# BLUETOOTH.net
KiCad netlist of a schematic drawn in Altium Designer
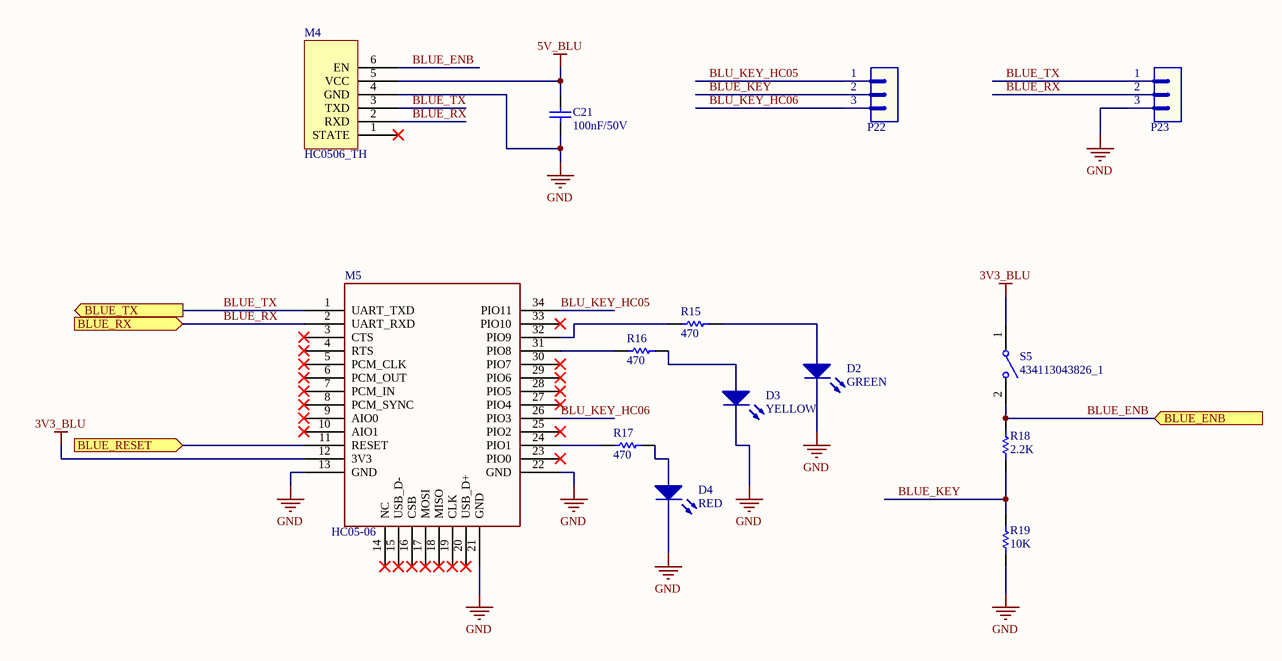
[diagram p0: BLUETOOTH.SchDoc]

(export (version "E")
  (design (tool "Eeschema 10.0.6"))
  (components
    (comp (ref "C21")
      (value "100nF/50V")
      (footprint "CAP-SM-0805")
      (description "CAP CER 1000PF 100V X7R 0805")
      (fields
        (field (name "MANUFACTURER") "Johanson Dielectrics Inc.")
        (field (name "MANUFACTURER PART NUMBER") "101X15W102MV4E")
      )
      (libsource (lib "PIF_ROBOT") (part "Cap-1nF-50V-0805"))
    )
    (comp (ref "D2") (value "GREEN") (footprint "LED_0805_Blue") (libsource (lib "PIF_C16_lib") (part "LED")))
    (comp (ref "D3")
      (value "YELLOW")
      (footprint "LED_0805_Blue")
      (libsource (lib "PIF_C16_lib") (part "LED"))
    )
    (comp (ref "D4") (value "RED") (footprint "LED_0805_Blue") (libsource (lib "PIF_C16_lib") (part "LED")))
    (comp (ref "M4")
      (value "HC0506_TH")
      (footprint "PCB_HC0506_TH:PCBComponent_1")
      (fields (field (name "LOCAL SUPPLIER PART NUMBER") "HS000882"))
      (libsource (lib "PIF_ROBOT") (part "HC0506_TH"))
    )
    (comp (ref "M5") (value "HC05-06") (footprint "HC05-06") (libsource (lib "PIF_ROBOT") (part "HC05-06")))
    (comp (ref "P22")
      (value "Header 3")
      (footprint "JP3")
      (description "Header, 3-Pin")
      (fields (field (name "PUBLISHER") "Altium Limited"))
      (libsource (lib "PIF_ROBOT") (part "Header 3"))
    )
    (comp (ref "P23")
      (value "Header 3")
      (footprint "JP3")
      (description "Header, 3-Pin")
      (fields (field (name "PUBLISHER") "Altium Limited"))
      (libsource (lib "PIF_ROBOT") (part "Header 3"))
    )
    (comp (ref "R15")
      (value "470")
      (footprint "RES-SM-0805")
      (description "RES 0 OHM JUMPER 0805")
      (fields
        (field (name "MANUFACTURER") "Vishay Dale")
        (field (name "MANUFACTURER PART NUMBER") "WSL080500000ZEA9")
      )
      (libsource (lib "PIF_ROBOT") (part "Res-0-0805"))
    )
    (comp (ref "R16")
      (value "470")
      (footprint "RES-SM-0805")
      (description "RES 0 OHM JUMPER 0805")
      (fields
        (field (name "MANUFACTURER") "Vishay Dale")
        (field (name "MANUFACTURER PART NUMBER") "WSL080500000ZEA9")
      )
      (libsource (lib "PIF_ROBOT") (part "Res-0-0805"))
    )
    (comp (ref "R17")
      (value "470")
      (footprint "RES-SM-0805")
      (description "RES 0 OHM JUMPER 0805")
      (fields
        (field (name "MANUFACTURER") "Vishay Dale")
        (field (name "MANUFACTURER PART NUMBER") "WSL080500000ZEA9")
      )
      (libsource (lib "PIF_ROBOT") (part "Res-0-0805"))
    )
    (comp (ref "R18")
      (value "2.2K")
      (footprint "RES-SM-0805")
      (description "RES 0 OHM JUMPER 0805")
      (fields
        (field (name "MANUFACTURER") "Vishay Dale")
        (field (name "MANUFACTURER PART NUMBER") "WSL080500000ZEA9")
      )
      (libsource (lib "PIF_ROBOT") (part "Res-0-0805"))
    )
    (comp (ref "R19")
      (value "10K")
      (footprint "RES-SM-0805")
      (description "RES 0 OHM JUMPER 0805")
      (fields
        (field (name "MANUFACTURER") "Vishay Dale")
        (field (name "MANUFACTURER PART NUMBER") "WSL080500000ZEA9")
      )
      (libsource (lib "PIF_ROBOT") (part "Res-0-0805"))
    )
    (comp (ref "S5")
      (value "434113043826_1")
      (footprint "434113043826")
      (description "WS-TASV J-Bend SMT Tact Switch 6x3.5mm, height 4.3mm, 260gf")
      (fields (field (name "PART NUMBER") "434113043826") (field (name "PUBLISHER") "Wurth Elektronik"))
      (libsource (lib "PIF_ROBOT") (part "434113043826_1"))
    )
  )
  (nets
    (net (code "1") (name "/BLUE_ENB") (class "Default")
      (node (ref "M4") (pin "6") (pinfunction "EN_6") (pintype "passive"))
      (node (ref "R18") (pin "1") (pinfunction "1_1") (pintype "passive"))
      (node (ref "S5") (pin "2") (pinfunction "2_2") (pintype "passive"))
    )
    (net (code "2") (name "/BLUE_KEY") (class "Default")
      (node (ref "P22") (pin "2") (pinfunction "2_2") (pintype "passive"))
      (node (ref "R18") (pin "2") (pinfunction "2_2") (pintype "passive"))
      (node (ref "R19") (pin "1") (pinfunction "1_1") (pintype "passive"))
    )
    (net (code "3") (name "/BLUE_RESET") (class "Default")
      (node (ref "M5") (pin "11") (pinfunction "RESET_11") (pintype "passive"))
    )
    (net (code "4") (name "/BLUE_RX") (class "Default")
      (node (ref "M4") (pin "2") (pinfunction "RXD_2") (pintype "passive"))
      (node (ref "M5") (pin "2") (pinfunction "UART_RXD_2") (pintype "passive"))
      (node (ref "P23") (pin "2") (pinfunction "2_2") (pintype "passive"))
    )
    (net (code "5") (name "/BLUE_TX") (class "Default")
      (node (ref "M4") (pin "3") (pinfunction "TXD_3") (pintype "passive"))
      (node (ref "M5") (pin "1") (pinfunction "UART_TXD_1") (pintype "passive"))
      (node (ref "P23") (pin "1") (pinfunction "1_1") (pintype "passive"))
    )
    (net (code "6") (name "/BLU_KEY_HC05") (class "Default")
      (node (ref "M5") (pin "34") (pinfunction "PIO11_34") (pintype "passive"))
      (node (ref "P22") (pin "1") (pinfunction "1_1") (pintype "passive"))
    )
    (net (code "7") (name "/BLU_KEY_HC06") (class "Default")
      (node (ref "M5") (pin "26") (pinfunction "PIO3_26") (pintype "passive"))
      (node (ref "P22") (pin "3") (pinfunction "3_3") (pintype "passive"))
    )
    (net (code "8") (name "3V3_BLU") (class "Default")
      (node (ref "M5") (pin "12") (pinfunction "3V3_12") (pintype "passive"))
      (node (ref "S5") (pin "1") (pinfunction "1_1") (pintype "passive"))
    )
    (net (code "9") (name "5V_BLU") (class "Default")
      (node (ref "C21") (pin "2") (pinfunction "2_2") (pintype "passive"))
      (node (ref "M4") (pin "5") (pinfunction "VCC_5") (pintype "passive"))
    )
    (net (code "10") (name "GND") (class "Default")
      (node (ref "C21") (pin "1") (pinfunction "1_1") (pintype "passive"))
      (node (ref "D2") (pin "2") (pinfunction "K_2") (pintype "passive"))
      (node (ref "D3") (pin "2") (pinfunction "K_2") (pintype "passive"))
      (node (ref "D4") (pin "2") (pinfunction "K_2") (pintype "passive"))
      (node (ref "M4") (pin "4") (pinfunction "GND_4") (pintype "passive"))
      (node (ref "M5") (pin "13") (pinfunction "GND_13") (pintype "passive"))
      (node (ref "M5") (pin "21") (pinfunction "GND_21") (pintype "passive"))
      (node (ref "M5") (pin "22") (pinfunction "GND_22") (pintype "passive"))
      (node (ref "P23") (pin "3") (pinfunction "3_3") (pintype "passive"))
      (node (ref "R19") (pin "2") (pinfunction "2_2") (pintype "passive"))
    )
    (net (code "11") (name "Net-(D2-A)") (class "Default")
      (node (ref "D2") (pin "1") (pinfunction "A_1") (pintype "passive"))
      (node (ref "R15") (pin "2") (pinfunction "2_2") (pintype "passive"))
    )
    (net (code "12") (name "Net-(D3-A)") (class "Default")
      (node (ref "D3") (pin "1") (pinfunction "A_1") (pintype "passive"))
      (node (ref "R16") (pin "2") (pinfunction "2_2") (pintype "passive"))
    )
    (net (code "13") (name "Net-(D4-A)") (class "Default")
      (node (ref "D4") (pin "1") (pinfunction "A_1") (pintype "passive"))
      (node (ref "R17") (pin "2") (pinfunction "2_2") (pintype "passive"))
    )
    (net (code "14") (name "Net-(M5-PIO1)") (class "Default")
      (node (ref "M5") (pin "24") (pinfunction "PIO1_24") (pintype "passive"))
      (node (ref "R17") (pin "1") (pinfunction "1_1") (pintype "passive"))
    )
    (net (code "15") (name "Net-(M5-PIO8)") (class "Default")
      (node (ref "M5") (pin "31") (pinfunction "PIO8_31") (pintype "passive"))
      (node (ref "R16") (pin "1") (pinfunction "1_1") (pintype "passive"))
    )
    (net (code "16") (name "Net-(M5-PIO9)") (class "Default")
      (node (ref "M5") (pin "32") (pinfunction "PIO9_32") (pintype "passive"))
      (node (ref "R15") (pin "1") (pinfunction "1_1") (pintype "passive"))
    )
    (net (code "17") (name "unconnected-(M4-STATE-Pad1)") (class "Default")
      (node (ref "M4") (pin "1") (pinfunction "STATE_1") (pintype "passive+no_connect"))
    )
    (net (code "18") (name "unconnected-(M5-AIO0-Pad9)") (class "Default")
      (node (ref "M5") (pin "9") (pinfunction "AIO0_9") (pintype "passive+no_connect"))
    )
    (net (code "19") (name "unconnected-(M5-AIO1-Pad10)") (class "Default")
      (node (ref "M5") (pin "10") (pinfunction "AIO1_10") (pintype "passive+no_connect"))
    )
    (net (code "20") (name "unconnected-(M5-CLK-Pad19)") (class "Default")
      (node (ref "M5") (pin "19") (pinfunction "CLK_19") (pintype "passive+no_connect"))
    )
    (net (code "21") (name "unconnected-(M5-CSB-Pad16)") (class "Default")
      (node (ref "M5") (pin "16") (pinfunction "CSB_16") (pintype "passive+no_connect"))
    )
    (net (code "22") (name "unconnected-(M5-CTS-Pad3)") (class "Default")
      (node (ref "M5") (pin "3") (pinfunction "CTS_3") (pintype "passive+no_connect"))
    )
    (net (code "23") (name "unconnected-(M5-MISO-Pad18)") (class "Default")
      (node (ref "M5") (pin "18") (pinfunction "MISO_18") (pintype "passive+no_connect"))
    )
    (net (code "24") (name "unconnected-(M5-MOSI-Pad17)") (class "Default")
      (node (ref "M5") (pin "17") (pinfunction "MOSI_17") (pintype "passive+no_connect"))
    )
    (net (code "25") (name "unconnected-(M5-NC-Pad14)") (class "Default")
      (node (ref "M5") (pin "14") (pinfunction "NC_14") (pintype "passive+no_connect"))
    )
    (net (code "26") (name "unconnected-(M5-PCM_CLK-Pad5)") (class "Default")
      (node (ref "M5") (pin "5") (pinfunction "PCM_CLK_5") (pintype "passive+no_connect"))
    )
    (net (code "27") (name "unconnected-(M5-PCM_IN-Pad7)") (class "Default")
      (node (ref "M5") (pin "7") (pinfunction "PCM_IN_7") (pintype "passive+no_connect"))
    )
    (net (code "28") (name "unconnected-(M5-PCM_OUT-Pad6)") (class "Default")
      (node (ref "M5") (pin "6") (pinfunction "PCM_OUT_6") (pintype "passive+no_connect"))
    )
    (net (code "29") (name "unconnected-(M5-PCM_SYNC-Pad8)") (class "Default")
      (node (ref "M5") (pin "8") (pinfunction "PCM_SYNC_8") (pintype "passive+no_connect"))
    )
    (net (code "30") (name "unconnected-(M5-PIO0-Pad23)") (class "Default")
      (node (ref "M5") (pin "23") (pinfunction "PIO0_23") (pintype "passive+no_connect"))
    )
    (net (code "31") (name "unconnected-(M5-PIO2-Pad25)") (class "Default")
      (node (ref "M5") (pin "25") (pinfunction "PIO2_25") (pintype "passive+no_connect"))
    )
    (net (code "32") (name "unconnected-(M5-PIO4-Pad27)") (class "Default")
      (node (ref "M5") (pin "27") (pinfunction "PIO4_27") (pintype "passive+no_connect"))
    )
    (net (code "33") (name "unconnected-(M5-PIO5-Pad28)") (class "Default")
      (node (ref "M5") (pin "28") (pinfunction "PIO5_28") (pintype "passive+no_connect"))
    )
    (net (code "34") (name "unconnected-(M5-PIO6-Pad29)") (class "Default")
      (node (ref "M5") (pin "29") (pinfunction "PIO6_29") (pintype "passive+no_connect"))
    )
    (net (code "35") (name "unconnected-(M5-PIO7-Pad30)") (class "Default")
      (node (ref "M5") (pin "30") (pinfunction "PIO7_30") (pintype "passive+no_connect"))
    )
    (net (code "36") (name "unconnected-(M5-PIO10-Pad33)") (class "Default")
      (node (ref "M5") (pin "33") (pinfunction "PIO10_33") (pintype "passive+no_connect"))
    )
    (net (code "37") (name "unconnected-(M5-RTS-Pad4)") (class "Default")
      (node (ref "M5") (pin "4") (pinfunction "RTS_4") (pintype "passive+no_connect"))
    )
    (net (code "38") (name "unconnected-(M5-USB_D+-Pad20)") (class "Default")
      (node (ref "M5") (pin "20") (pinfunction "USB_D+_20") (pintype "passive+no_connect"))
    )
    (net (code "39") (name "unconnected-(M5-USB_D--Pad15)") (class "Default")
      (node (ref "M5") (pin "15") (pinfunction "USB_D-_15") (pintype "passive+no_connect"))
    )
  )
)
